# LED_CUBE.net
KiCad netlist of a schematic drawn in EAGLE
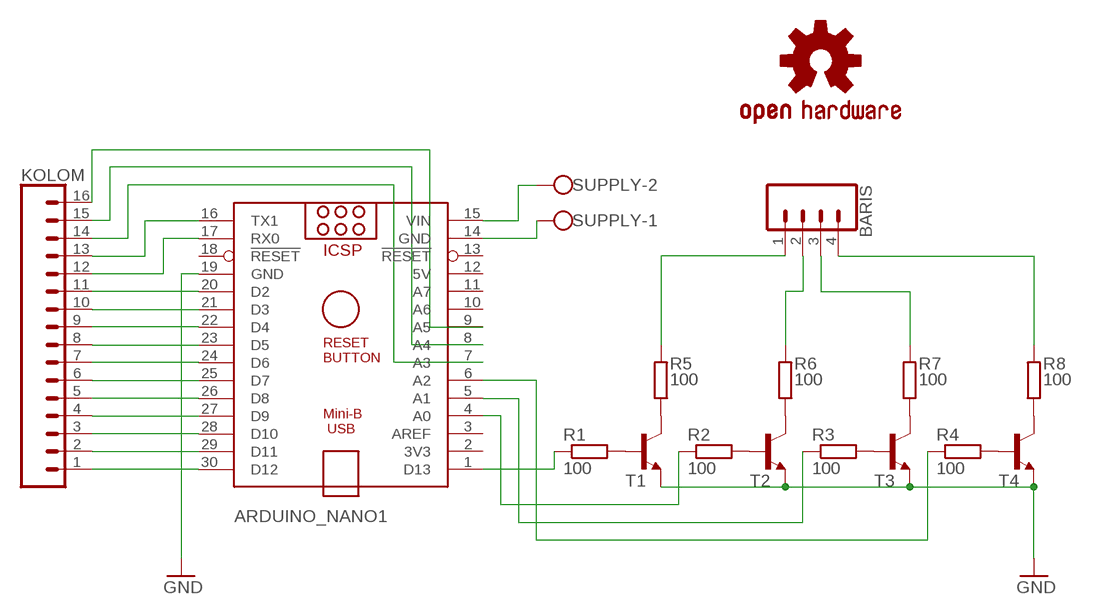
[diagram p0: schematic, sheet 1]

(export (version "E")
  (design (tool "Eeschema 10.0.6"))
  (components
    (comp (ref "ARDUINO_NANO1")
      (value "ARDUINO_NANO")
      (footprint "eagle-import:ARDUINO_NANO")
      (libsource (lib "eagle-import") (part "ARDUINO_NANO"))
    )
    (comp (ref "BARIS")
      (value "CONN_04LONGPADS")
      (footprint "eagle-import:1X04_LONGPADS")
      (libsource (lib "eagle-import") (part "CONN_04LONGPADS"))
    )
    (comp (ref "KOLOM")
      (value "CONN_16LONGPADS")
      (footprint "eagle-import:1X16_LONGPADS")
      (libsource (lib "eagle-import") (part "CONN_16LONGPADS"))
    )
    (comp (ref "LOGO2")
      (value "OSHW-LOGOL-COPPER")
      (footprint "eagle-import:OSHW-LOGO-L_COPPER")
      (libsource (lib "eagle-import") (part "OSHW-LOGOL-COPPER"))
    )
    (comp (ref "R1")
      (value "100")
      (footprint "eagle-import:0411_15")
      (libsource (lib "eagle-import") (part "R-EU_0411/15"))
    )
    (comp (ref "R2")
      (value "100")
      (footprint "eagle-import:0411_15")
      (libsource (lib "eagle-import") (part "R-EU_0411/15"))
    )
    (comp (ref "R3")
      (value "100")
      (footprint "eagle-import:0411_15")
      (libsource (lib "eagle-import") (part "R-EU_0411/15"))
    )
    (comp (ref "R4")
      (value "100")
      (footprint "eagle-import:0411_15")
      (libsource (lib "eagle-import") (part "R-EU_0411/15"))
    )
    (comp (ref "R5")
      (value "100")
      (footprint "eagle-import:0309_10")
      (libsource (lib "eagle-import") (part "R-EU_0309/10"))
    )
    (comp (ref "R6")
      (value "100")
      (footprint "eagle-import:0309_10")
      (libsource (lib "eagle-import") (part "R-EU_0309/10"))
    )
    (comp (ref "R7")
      (value "100")
      (footprint "eagle-import:0309_10")
      (libsource (lib "eagle-import") (part "R-EU_0309/10"))
    )
    (comp (ref "R8")
      (value "100")
      (footprint "eagle-import:0309_10")
      (libsource (lib "eagle-import") (part "R-EU_0309/10"))
    )
    (comp (ref "SUPPLY")
      (value "W237-102")
      (footprint "eagle-import:W237-102")
      (fields (field (name "MPN") "237-102"))
      (libsource (lib "eagle-import") (part "W237-102"))
    )
    (comp (ref "T1")
      (value "-NPN-TO92-EBC")
      (footprint "eagle-import:TO92-EBC")
      (libsource (lib "eagle-import") (part "-NPN-TO92-EBC"))
    )
    (comp (ref "T2")
      (value "-NPN-TO92-EBC")
      (footprint "eagle-import:TO92-EBC")
      (libsource (lib "eagle-import") (part "-NPN-TO92-EBC"))
    )
    (comp (ref "T3")
      (value "-NPN-TO92-EBC")
      (footprint "eagle-import:TO92-EBC")
      (libsource (lib "eagle-import") (part "-NPN-TO92-EBC"))
    )
    (comp (ref "T4")
      (value "-NPN-TO92-EBC")
      (footprint "eagle-import:TO92-EBC")
      (libsource (lib "eagle-import") (part "-NPN-TO92-EBC"))
    )
  )
  (nets
    (net (code "1") (name "/5V") (class "Default")
      (node (ref "ARDUINO_NANO1") (pin "12") (pinfunction "5V_12") (pintype "power_in"))
    )
    (net (code "2") (name "GND") (class "Default")
      (node (ref "ARDUINO_NANO1") (pin "19") (pinfunction "GND_19") (pintype "power_in"))
      (node (ref "T1") (pin "E") (pinfunction "E_E") (pintype "passive"))
      (node (ref "T2") (pin "E") (pinfunction "E_E") (pintype "passive"))
      (node (ref "T3") (pin "E") (pinfunction "E_E") (pintype "passive"))
      (node (ref "T4") (pin "E") (pinfunction "E_E") (pintype "passive"))
    )
    (net (code "3") (name "Net-(ARDUINO_NANO1-A0)") (class "Default")
      (node (ref "ARDUINO_NANO1") (pin "4") (pinfunction "A0_4") (pintype "bidirectional"))
      (node (ref "R2") (pin "1") (pinfunction "1_1") (pintype "passive"))
    )
    (net (code "4") (name "Net-(ARDUINO_NANO1-A1)") (class "Default")
      (node (ref "ARDUINO_NANO1") (pin "5") (pinfunction "A1_5") (pintype "bidirectional"))
      (node (ref "R3") (pin "1") (pinfunction "1_1") (pintype "passive"))
    )
    (net (code "5") (name "Net-(ARDUINO_NANO1-A2)") (class "Default")
      (node (ref "ARDUINO_NANO1") (pin "6") (pinfunction "A2_6") (pintype "bidirectional"))
      (node (ref "R4") (pin "1") (pinfunction "1_1") (pintype "passive"))
    )
    (net (code "6") (name "Net-(ARDUINO_NANO1-A3)") (class "Default")
      (node (ref "ARDUINO_NANO1") (pin "7") (pinfunction "A3_7") (pintype "bidirectional"))
      (node (ref "KOLOM") (pin "14") (pinfunction "14_14") (pintype "passive"))
    )
    (net (code "7") (name "Net-(ARDUINO_NANO1-A4)") (class "Default")
      (node (ref "ARDUINO_NANO1") (pin "8") (pinfunction "A4_8") (pintype "bidirectional"))
      (node (ref "KOLOM") (pin "15") (pinfunction "15_15") (pintype "passive"))
    )
    (net (code "8") (name "Net-(ARDUINO_NANO1-A5)") (class "Default")
      (node (ref "ARDUINO_NANO1") (pin "9") (pinfunction "A5_9") (pintype "bidirectional"))
      (node (ref "KOLOM") (pin "16") (pinfunction "16_16") (pintype "passive"))
    )
    (net (code "9") (name "Net-(ARDUINO_NANO1-D2)") (class "Default")
      (node (ref "ARDUINO_NANO1") (pin "20") (pinfunction "D2_20") (pintype "bidirectional"))
      (node (ref "KOLOM") (pin "11") (pinfunction "11_11") (pintype "passive"))
    )
    (net (code "10") (name "Net-(ARDUINO_NANO1-D3)") (class "Default")
      (node (ref "ARDUINO_NANO1") (pin "21") (pinfunction "D3_21") (pintype "bidirectional"))
      (node (ref "KOLOM") (pin "10") (pinfunction "10_10") (pintype "passive"))
    )
    (net (code "11") (name "Net-(ARDUINO_NANO1-D4)") (class "Default")
      (node (ref "ARDUINO_NANO1") (pin "22") (pinfunction "D4_22") (pintype "bidirectional"))
      (node (ref "KOLOM") (pin "9") (pinfunction "9_9") (pintype "passive"))
    )
    (net (code "12") (name "Net-(ARDUINO_NANO1-D5)") (class "Default")
      (node (ref "ARDUINO_NANO1") (pin "23") (pinfunction "D5_23") (pintype "bidirectional"))
      (node (ref "KOLOM") (pin "8") (pinfunction "8_8") (pintype "passive"))
    )
    (net (code "13") (name "Net-(ARDUINO_NANO1-D6)") (class "Default")
      (node (ref "ARDUINO_NANO1") (pin "24") (pinfunction "D6_24") (pintype "bidirectional"))
      (node (ref "KOLOM") (pin "7") (pinfunction "7_7") (pintype "passive"))
    )
    (net (code "14") (name "Net-(ARDUINO_NANO1-D7)") (class "Default")
      (node (ref "ARDUINO_NANO1") (pin "25") (pinfunction "D7_25") (pintype "bidirectional"))
      (node (ref "KOLOM") (pin "6") (pinfunction "6_6") (pintype "passive"))
    )
    (net (code "15") (name "Net-(ARDUINO_NANO1-D8)") (class "Default")
      (node (ref "ARDUINO_NANO1") (pin "26") (pinfunction "D8_26") (pintype "bidirectional"))
      (node (ref "KOLOM") (pin "5") (pinfunction "5_5") (pintype "passive"))
    )
    (net (code "16") (name "Net-(ARDUINO_NANO1-D9)") (class "Default")
      (node (ref "ARDUINO_NANO1") (pin "27") (pinfunction "D9_27") (pintype "bidirectional"))
      (node (ref "KOLOM") (pin "4") (pinfunction "4_4") (pintype "passive"))
    )
    (net (code "17") (name "Net-(ARDUINO_NANO1-D10)") (class "Default")
      (node (ref "ARDUINO_NANO1") (pin "28") (pinfunction "D10_28") (pintype "bidirectional"))
      (node (ref "KOLOM") (pin "3") (pinfunction "3_3") (pintype "passive"))
    )
    (net (code "18") (name "Net-(ARDUINO_NANO1-D11)") (class "Default")
      (node (ref "ARDUINO_NANO1") (pin "29") (pinfunction "D11_29") (pintype "bidirectional"))
      (node (ref "KOLOM") (pin "2") (pinfunction "2_2") (pintype "passive"))
    )
    (net (code "19") (name "Net-(ARDUINO_NANO1-D12)") (class "Default")
      (node (ref "ARDUINO_NANO1") (pin "30") (pinfunction "D12_30") (pintype "bidirectional"))
      (node (ref "KOLOM") (pin "1") (pinfunction "1_1") (pintype "passive"))
    )
    (net (code "20") (name "Net-(ARDUINO_NANO1-D13)") (class "Default")
      (node (ref "ARDUINO_NANO1") (pin "1") (pinfunction "D13_1") (pintype "bidirectional"))
      (node (ref "R1") (pin "1") (pinfunction "1_1") (pintype "passive"))
    )
    (net (code "21") (name "Net-(ARDUINO_NANO1-RX0)") (class "Default")
      (node (ref "ARDUINO_NANO1") (pin "17") (pinfunction "RX0_17") (pintype "bidirectional"))
      (node (ref "KOLOM") (pin "12") (pinfunction "12_12") (pintype "passive"))
    )
    (net (code "22") (name "Net-(ARDUINO_NANO1-TX1)") (class "Default")
      (node (ref "ARDUINO_NANO1") (pin "16") (pinfunction "TX1_16") (pintype "bidirectional"))
      (node (ref "KOLOM") (pin "13") (pinfunction "13_13") (pintype "passive"))
    )
    (net (code "23") (name "Net-(ARDUINO_NANO1-VIN)") (class "Default")
      (node (ref "ARDUINO_NANO1") (pin "15") (pinfunction "VIN_15") (pintype "power_in"))
      (node (ref "SUPPLY") (pin "2") (pinfunction "KL_2") (pintype "passive"))
    )
    (net (code "24") (name "Net-(BARIS-Pad1)") (class "Default")
      (node (ref "BARIS") (pin "1") (pinfunction "1_1") (pintype "passive"))
      (node (ref "R5") (pin "2") (pinfunction "2_2") (pintype "passive"))
    )
    (net (code "25") (name "Net-(BARIS-Pad2)") (class "Default")
      (node (ref "BARIS") (pin "2") (pinfunction "2_2") (pintype "passive"))
      (node (ref "R6") (pin "2") (pinfunction "2_2") (pintype "passive"))
    )
    (net (code "26") (name "Net-(BARIS-Pad3)") (class "Default")
      (node (ref "BARIS") (pin "3") (pinfunction "3_3") (pintype "passive"))
      (node (ref "R7") (pin "2") (pinfunction "2_2") (pintype "passive"))
    )
    (net (code "27") (name "Net-(BARIS-Pad4)") (class "Default")
      (node (ref "BARIS") (pin "4") (pinfunction "4_4") (pintype "passive"))
      (node (ref "R8") (pin "2") (pinfunction "2_2") (pintype "passive"))
    )
    (net (code "28") (name "Net-(R1-Pad2)") (class "Default")
      (node (ref "R1") (pin "2") (pinfunction "2_2") (pintype "passive"))
      (node (ref "T1") (pin "B") (pinfunction "B_B") (pintype "passive"))
    )
    (net (code "29") (name "Net-(R2-Pad2)") (class "Default")
      (node (ref "R2") (pin "2") (pinfunction "2_2") (pintype "passive"))
      (node (ref "T2") (pin "B") (pinfunction "B_B") (pintype "passive"))
    )
    (net (code "30") (name "Net-(R3-Pad2)") (class "Default")
      (node (ref "R3") (pin "2") (pinfunction "2_2") (pintype "passive"))
      (node (ref "T3") (pin "B") (pinfunction "B_B") (pintype "passive"))
    )
    (net (code "31") (name "Net-(R4-Pad2)") (class "Default")
      (node (ref "R4") (pin "2") (pinfunction "2_2") (pintype "passive"))
      (node (ref "T4") (pin "B") (pinfunction "B_B") (pintype "passive"))
    )
    (net (code "32") (name "Net-(R5-Pad1)") (class "Default")
      (node (ref "R5") (pin "1") (pinfunction "1_1") (pintype "passive"))
      (node (ref "T1") (pin "C") (pinfunction "C_C") (pintype "passive"))
    )
    (net (code "33") (name "Net-(R6-Pad1)") (class "Default")
      (node (ref "R6") (pin "1") (pinfunction "1_1") (pintype "passive"))
      (node (ref "T2") (pin "C") (pinfunction "C_C") (pintype "passive"))
    )
    (net (code "34") (name "Net-(R7-Pad1)") (class "Default")
      (node (ref "R7") (pin "1") (pinfunction "1_1") (pintype "passive"))
      (node (ref "T3") (pin "C") (pinfunction "C_C") (pintype "passive"))
    )
    (net (code "35") (name "Net-(R8-Pad1)") (class "Default")
      (node (ref "R8") (pin "1") (pinfunction "1_1") (pintype "passive"))
      (node (ref "T4") (pin "C") (pinfunction "C_C") (pintype "passive"))
    )
    (net (code "36") (name "Net-(SUPPLYA-KL)") (class "Default")
      (node (ref "ARDUINO_NANO1") (pin "14") (pinfunction "GND_14") (pintype "power_in"))
      (node (ref "SUPPLY") (pin "1") (pinfunction "KL_1") (pintype "passive"))
    )
    (net (code "37") (name "unconnected-(ARDUINO_NANO1-3V3-Pad2)") (class "Default")
      (node (ref "ARDUINO_NANO1") (pin "2") (pinfunction "3V3_2") (pintype "output"))
    )
    (net (code "38") (name "unconnected-(ARDUINO_NANO1-A6-Pad10)") (class "Default")
      (node (ref "ARDUINO_NANO1") (pin "10") (pinfunction "A6_10") (pintype "bidirectional"))
    )
    (net (code "39") (name "unconnected-(ARDUINO_NANO1-A7-Pad11)") (class "Default")
      (node (ref "ARDUINO_NANO1") (pin "11") (pinfunction "A7_11") (pintype "bidirectional"))
    )
    (net (code "40") (name "unconnected-(ARDUINO_NANO1-AREF-Pad3)") (class "Default")
      (node (ref "ARDUINO_NANO1") (pin "3") (pinfunction "AREF_3") (pintype "input"))
    )
    (net (code "41") (name "unconnected-(ARDUINO_NANO1-~{RESET}-Pad13)") (class "Default")
      (node (ref "ARDUINO_NANO1") (pin "13") (pinfunction "~{RESET}_13") (pintype "input"))
    )
    (net (code "42") (name "unconnected-(ARDUINO_NANO1-~{RESET}-Pad18)") (class "Default")
      (node (ref "ARDUINO_NANO1") (pin "18") (pinfunction "~{RESET}_18") (pintype "input"))
    )
  )
)
